# mini32.net
KiCad netlist of a schematic drawn in EAGLE
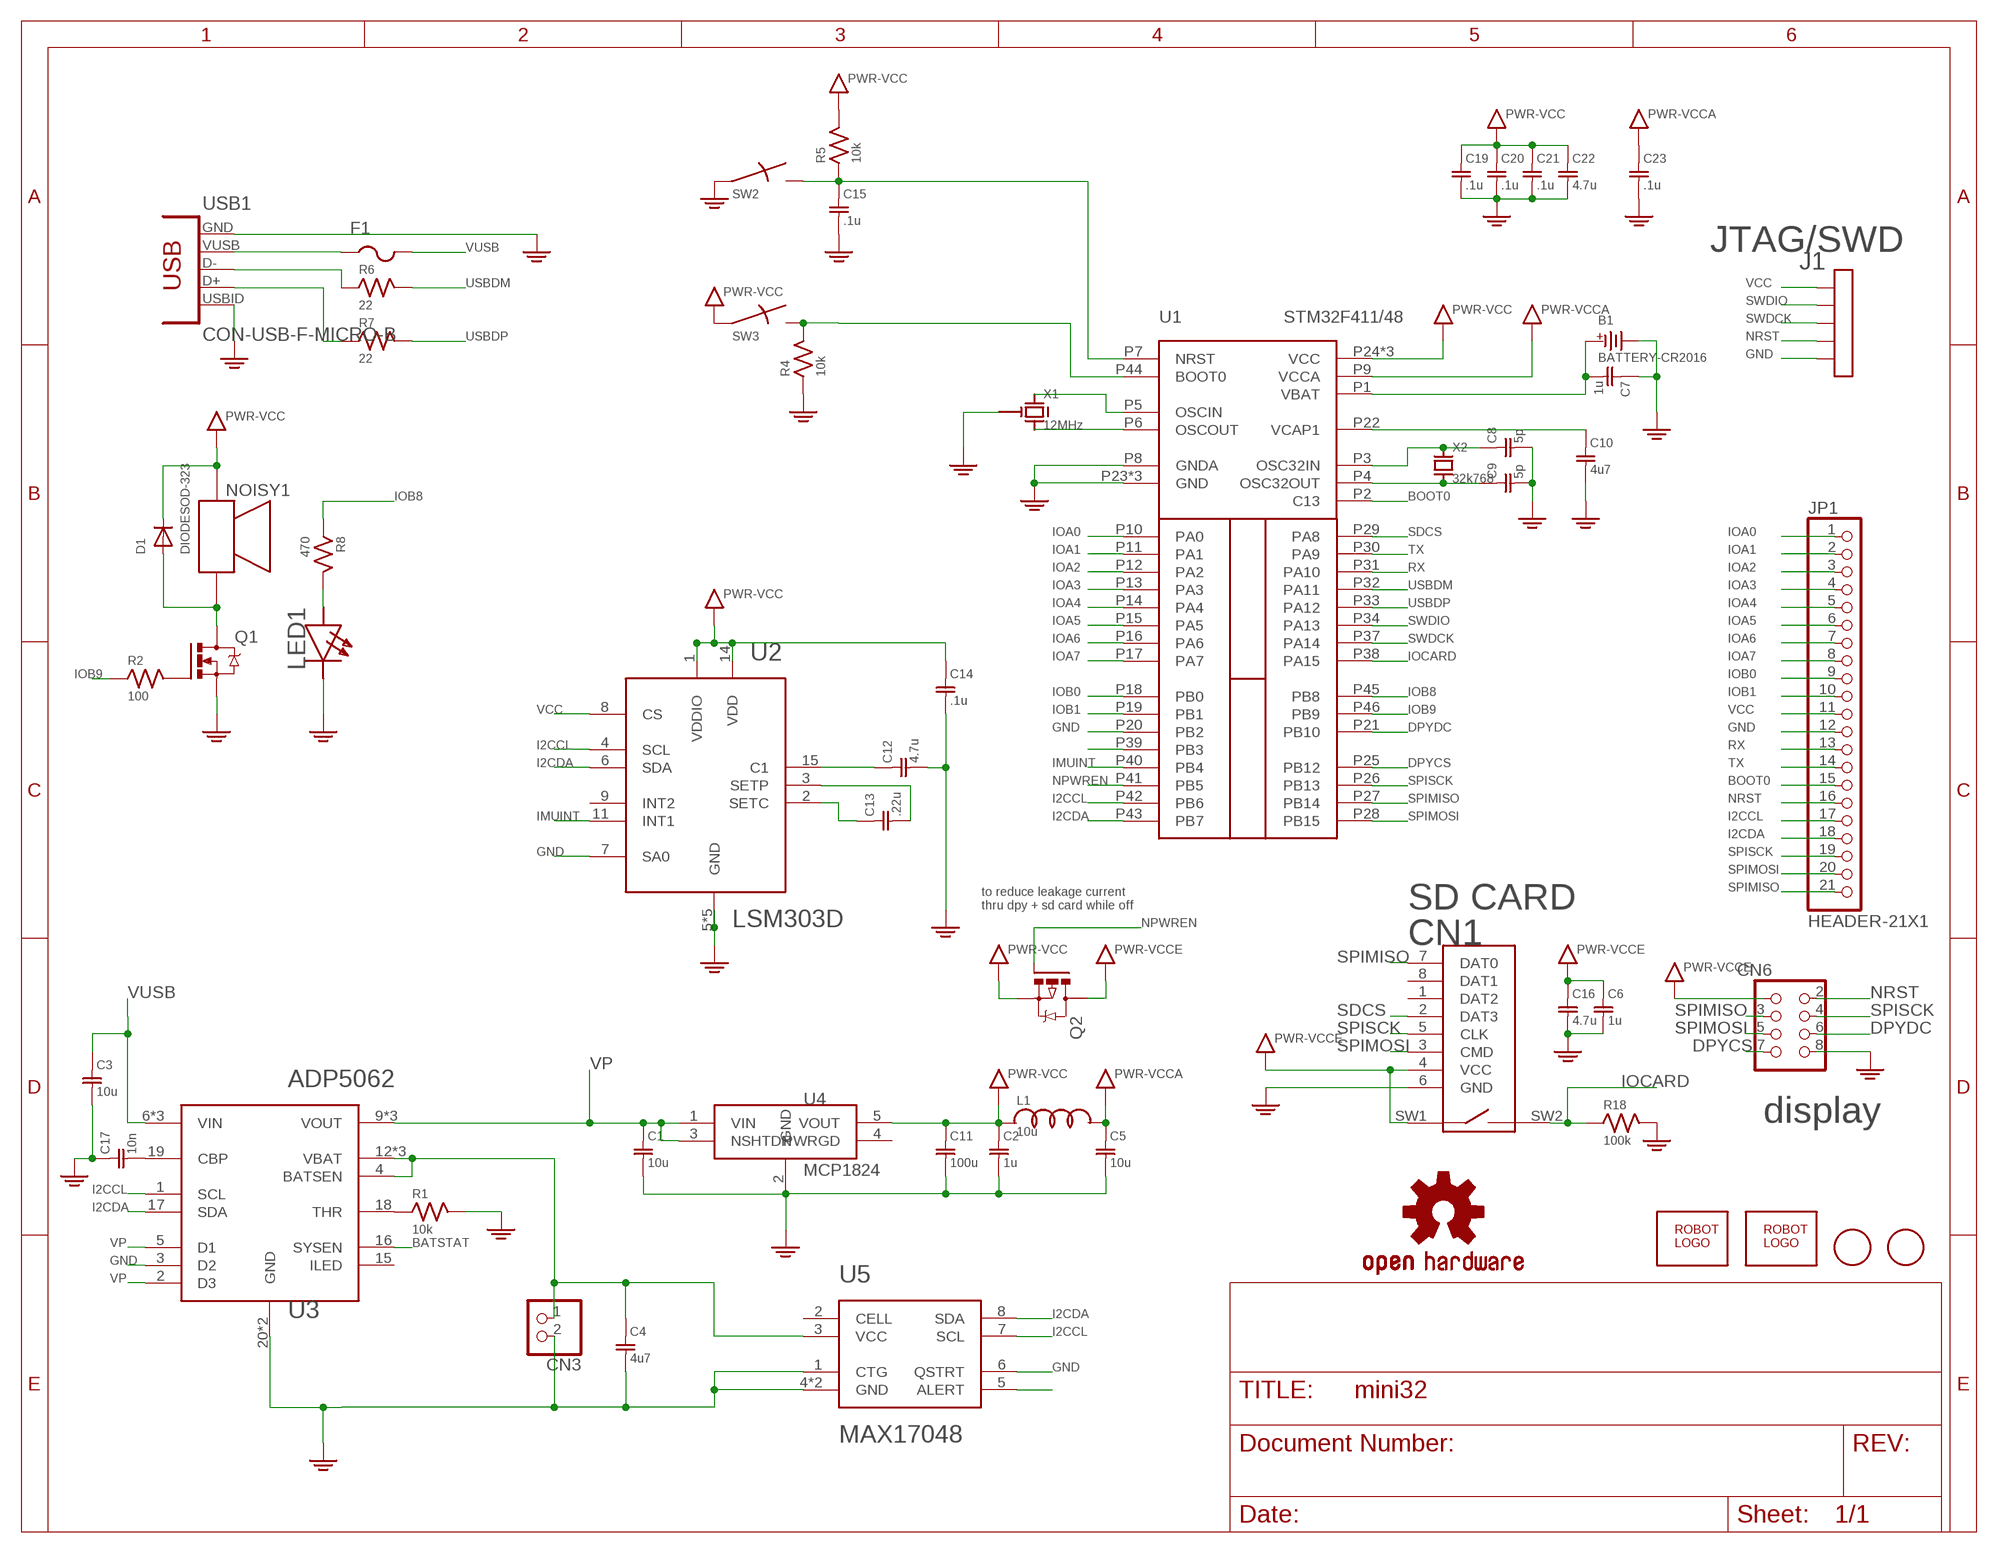
[diagram p0: schematic, sheet 1]

(export (version "E")
  (design (tool "Eeschema 10.0.6"))
  (components
    (comp (ref "B1")
      (value "BATTERY-CR2016")
      (footprint "eagle-import:CR1216")
      (libsource (lib "eagle-import") (part "BATTERY-CR2016"))
    )
    (comp (ref "C1")
      (value "10u")
      (footprint "eagle-import:SMD0603")
      (libsource (lib "eagle-import") (part "C0603"))
    )
    (comp (ref "C2")
      (value "1u")
      (footprint "eagle-import:SMD0603")
      (libsource (lib "eagle-import") (part "C0603"))
    )
    (comp (ref "C3")
      (value "10u")
      (footprint "eagle-import:SMD0603")
      (libsource (lib "eagle-import") (part "C0603"))
    )
    (comp (ref "C4")
      (value "4u7")
      (footprint "eagle-import:SMD0603")
      (libsource (lib "eagle-import") (part "C0603"))
    )
    (comp (ref "C5")
      (value "10u")
      (footprint "eagle-import:SMD0603")
      (libsource (lib "eagle-import") (part "C0603"))
    )
    (comp (ref "C6")
      (value "1u")
      (footprint "eagle-import:SMD0603")
      (libsource (lib "eagle-import") (part "C0603"))
    )
    (comp (ref "C7")
      (value "1u")
      (footprint "eagle-import:SMD0603")
      (libsource (lib "eagle-import") (part "C0603"))
    )
    (comp (ref "C8")
      (value "5p")
      (footprint "eagle-import:SMD0603")
      (libsource (lib "eagle-import") (part "C0603"))
    )
    (comp (ref "C9")
      (value "5p")
      (footprint "eagle-import:SMD0603")
      (libsource (lib "eagle-import") (part "C0603"))
    )
    (comp (ref "C10")
      (value "4u7")
      (footprint "eagle-import:SMD0603")
      (libsource (lib "eagle-import") (part "C0603"))
    )
    (comp (ref "C11")
      (value "100u")
      (footprint "eagle-import:SMD1210")
      (libsource (lib "eagle-import") (part "C1210"))
    )
    (comp (ref "C12")
      (value "4.7u")
      (footprint "eagle-import:SMD0603")
      (libsource (lib "eagle-import") (part "C0603"))
    )
    (comp (ref "C13")
      (value ".22u")
      (footprint "eagle-import:SMD0603")
      (libsource (lib "eagle-import") (part "C0603"))
    )
    (comp (ref "C14")
      (value ".1u")
      (footprint "eagle-import:SMD0603")
      (libsource (lib "eagle-import") (part "C0603"))
    )
    (comp (ref "C15")
      (value ".1u")
      (footprint "eagle-import:SMD0603")
      (libsource (lib "eagle-import") (part "C0603"))
    )
    (comp (ref "C16")
      (value "4.7u")
      (footprint "eagle-import:SMD0603")
      (libsource (lib "eagle-import") (part "C0603"))
    )
    (comp (ref "C17")
      (value "10n")
      (footprint "eagle-import:SMD0603")
      (libsource (lib "eagle-import") (part "C0603"))
    )
    (comp (ref "C19")
      (value ".1u")
      (footprint "eagle-import:SMD0603")
      (libsource (lib "eagle-import") (part "C0603"))
    )
    (comp (ref "C20")
      (value ".1u")
      (footprint "eagle-import:SMD0603")
      (libsource (lib "eagle-import") (part "C0603"))
    )
    (comp (ref "C21")
      (value ".1u")
      (footprint "eagle-import:SMD0603")
      (libsource (lib "eagle-import") (part "C0603"))
    )
    (comp (ref "C22")
      (value "4.7u")
      (footprint "eagle-import:SMD0603")
      (libsource (lib "eagle-import") (part "C0603"))
    )
    (comp (ref "C23")
      (value ".1u")
      (footprint "eagle-import:SMD0603")
      (libsource (lib "eagle-import") (part "C0603"))
    )
    (comp (ref "CN1")
      (value "MICROSDPLAIN")
      (footprint "eagle-import:MICROSD_MOLEX_FRONT_PLAIN")
      (libsource (lib "eagle-import") (part "MICROSDPLAIN"))
    )
    (comp (ref "CN3")
      (value "JST_2PIN-SMT-RA")
      (footprint "eagle-import:JST-PH-2-SMT-RA")
      (libsource (lib "eagle-import") (part "JST_2PIN-SMT-RA"))
    )
    (comp (ref "CN6")
      (value "HEADER-2X4")
      (footprint "eagle-import:HEADER-2X04")
      (libsource (lib "eagle-import") (part "HEADER-2X4"))
    )
    (comp (ref "D1")
      (value "DIODESOD-323")
      (footprint "eagle-import:SOD-323")
      (libsource (lib "eagle-import") (part "DIODESOD-323"))
    )
    (comp (ref "F1")
      (value "PTCFUSE-1206")
      (footprint "eagle-import:R1206")
      (libsource (lib "eagle-import") (part "PTCFUSE-1206"))
    )
    (comp (ref "J1")
      (value "HEADER-5X1")
      (footprint "eagle-import:M127-5X1")
      (libsource (lib "eagle-import") (part "HEADER-5X1"))
    )
    (comp (ref "JP1")
      (value "HEADER-21X1")
      (footprint "eagle-import:HEADER-21X1-PTH")
      (libsource (lib "eagle-import") (part "HEADER-21X1"))
    )
    (comp (ref "L1")
      (value "10u")
      (footprint "eagle-import:SMD0603")
      (libsource (lib "eagle-import") (part "LSMD0603"))
    )
    (comp (ref "LED1")
      (value "white")
      (footprint "eagle-import:SMD0603D")
      (libsource (lib "eagle-import") (part "LED"))
    )
    (comp (ref "LOGO1")
      (value "OSHW-LOGOM")
      (footprint "eagle-import:OSHW-LOGO-M")
      (libsource (lib "eagle-import") (part "OSHW-LOGOM"))
    )
    (comp (ref "NOISY1")
      (value "PUI-5040")
      (footprint "eagle-import:PUI-0540")
      (libsource (lib "eagle-import") (part "PUI-5040"))
    )
    (comp (ref "Q1")
      (value "IRLML6344TRPBF")
      (footprint "eagle-import:SOT-23")
      (libsource (lib "eagle-import") (part "MOSFETSOT-23"))
    )
    (comp (ref "Q2")
      (value "DMP2035U-7")
      (footprint "eagle-import:SOT-23")
      (libsource (lib "eagle-import") (part "MOSFET-P"))
    )
    (comp (ref "R1")
      (value "10k")
      (footprint "eagle-import:SMD0603")
      (libsource (lib "eagle-import") (part "R0603"))
    )
    (comp (ref "R2")
      (value "100")
      (footprint "eagle-import:SMD0603")
      (libsource (lib "eagle-import") (part "R0603"))
    )
    (comp (ref "R4")
      (value "10k")
      (footprint "eagle-import:SMD0603")
      (libsource (lib "eagle-import") (part "R0603"))
    )
    (comp (ref "R5")
      (value "10k")
      (footprint "eagle-import:SMD0603")
      (libsource (lib "eagle-import") (part "R0603"))
    )
    (comp (ref "R6")
      (value "22")
      (footprint "eagle-import:SMD0603")
      (libsource (lib "eagle-import") (part "R0603"))
    )
    (comp (ref "R7")
      (value "22")
      (footprint "eagle-import:SMD0603")
      (libsource (lib "eagle-import") (part "R0603"))
    )
    (comp (ref "R8")
      (value "470")
      (footprint "eagle-import:SMD0603")
      (libsource (lib "eagle-import") (part "R0603"))
    )
    (comp (ref "R18")
      (value "100k")
      (footprint "eagle-import:SMD0603")
      (libsource (lib "eagle-import") (part "R0603"))
    )
    (comp (ref "SW2")
      (value "SWITCHKMR211")
      (footprint "eagle-import:KMR211")
      (libsource (lib "eagle-import") (part "SWITCHKMR211"))
    )
    (comp (ref "SW3")
      (value "SWITCHKMR211")
      (footprint "eagle-import:KMR211")
      (libsource (lib "eagle-import") (part "SWITCHKMR211"))
    )
    (comp (ref "U$1")
      (value "ROBOTMAN-LOGO2")
      (footprint "eagle-import:ROBOTMAN-LOGO2")
      (libsource (lib "eagle-import") (part "ROBOTMAN-LOGO2"))
    )
    (comp (ref "U$2")
      (value "FIDUCIAL")
      (footprint "eagle-import:FIDUCIAL_1MM")
      (libsource (lib "eagle-import") (part "FIDUCIAL"))
    )
    (comp (ref "U$3")
      (value "FIDUCIAL")
      (footprint "eagle-import:FIDUCIAL_1MM")
      (libsource (lib "eagle-import") (part "FIDUCIAL"))
    )
    (comp (ref "U$4")
      (value "ROBOTMAN-LOGO2")
      (footprint "eagle-import:ROBOTMAN-LOGO2")
      (libsource (lib "eagle-import") (part "ROBOTMAN-LOGO2"))
    )
    (comp (ref "U1")
      (value "STM32F411/48")
      (footprint "eagle-import:UQPFN48")
      (libsource (lib "eagle-import") (part "STM32F411/48"))
    )
    (comp (ref "U2")
      (value "LSM303D")
      (footprint "eagle-import:LGA16A")
      (libsource (lib "eagle-import") (part "LSM303D"))
    )
    (comp (ref "U3")
      (value "ADP5062")
      (footprint "eagle-import:LGA20P")
      (libsource (lib "eagle-import") (part "ADP5062"))
    )
    (comp (ref "U4")
      (value "MCP1824")
      (footprint "eagle-import:SOT-23-5")
      (libsource (lib "eagle-import") (part "MCP1824"))
    )
    (comp (ref "U5")
      (value "MAX17048")
      (footprint "eagle-import:TDFN8EP")
      (libsource (lib "eagle-import") (part "MAX17048"))
    )
    (comp (ref "USB1")
      (value "CON-USB-F-MICRO-B")
      (footprint "eagle-import:CONN_USB_MICRO-B")
      (libsource (lib "eagle-import") (part "CON-USB-F-MICRO-B"))
    )
    (comp (ref "X1")
      (value "12MHz")
      (footprint "eagle-import:RESONATOR-CSTCE")
      (libsource (lib "eagle-import") (part "RESONATORCTCE"))
    )
    (comp (ref "X2")
      (value "32k768")
      (footprint "eagle-import:XTAL-32X15")
      (libsource (lib "eagle-import") (part "XTAL32X15"))
    )
  )
  (nets
    (net (code "1") (name "/BATSTAT") (class "Default")
      (node (ref "U3") (pin "16") (pinfunction "SYSEN_16") (pintype "bidirectional"))
    )
    (net (code "2") (name "/BOOT0") (class "Default")
      (node (ref "JP1") (pin "15") (pinfunction "15_15") (pintype "passive"))
      (node (ref "R4") (pin "2") (pinfunction "P$2_2") (pintype "passive"))
      (node (ref "SW3") (pin "2") (pinfunction "P$2_2") (pintype "passive"))
      (node (ref "SW3") (pin "4") (pinfunction "P$2_4") (pintype "passive"))
      (node (ref "U1") (pin "P2") (pinfunction "C13_P2") (pintype "bidirectional"))
      (node (ref "U1") (pin "P44") (pinfunction "BOOT0_P44") (pintype "bidirectional"))
    )
    (net (code "3") (name "/DPYCS") (class "Default")
      (node (ref "CN6") (pin "7") (pinfunction "P$7_7") (pintype "passive"))
      (node (ref "U1") (pin "P25") (pinfunction "PB12_P25") (pintype "bidirectional"))
    )
    (net (code "4") (name "/DPYDC") (class "Default")
      (node (ref "CN6") (pin "6") (pinfunction "P$6_6") (pintype "passive"))
      (node (ref "U1") (pin "P21") (pinfunction "PB10_P21") (pintype "bidirectional"))
    )
    (net (code "5") (name "/I2CCL") (class "Default")
      (node (ref "JP1") (pin "17") (pinfunction "17_17") (pintype "passive"))
      (node (ref "U1") (pin "P42") (pinfunction "PB6_P42") (pintype "bidirectional"))
      (node (ref "U2") (pin "4") (pinfunction "SCL_4") (pintype "bidirectional"))
      (node (ref "U3") (pin "1") (pinfunction "SCL_1") (pintype "bidirectional"))
      (node (ref "U5") (pin "7") (pinfunction "SCL_7") (pintype "bidirectional"))
    )
    (net (code "6") (name "/I2CDA") (class "Default")
      (node (ref "JP1") (pin "18") (pinfunction "18_18") (pintype "passive"))
      (node (ref "U1") (pin "P43") (pinfunction "PB7_P43") (pintype "bidirectional"))
      (node (ref "U2") (pin "6") (pinfunction "SDA_6") (pintype "bidirectional"))
      (node (ref "U3") (pin "17") (pinfunction "SDA_17") (pintype "bidirectional"))
      (node (ref "U5") (pin "8") (pinfunction "SDA_8") (pintype "bidirectional"))
    )
    (net (code "7") (name "/IMUINT") (class "Default")
      (node (ref "U1") (pin "P40") (pinfunction "PB4_P40") (pintype "bidirectional"))
      (node (ref "U2") (pin "11") (pinfunction "INT1_11") (pintype "output"))
    )
    (net (code "8") (name "/IOA0") (class "Default")
      (node (ref "JP1") (pin "1") (pinfunction "1_1") (pintype "passive"))
      (node (ref "U1") (pin "P10") (pinfunction "PA0_P10") (pintype "bidirectional"))
    )
    (net (code "9") (name "/IOA1") (class "Default")
      (node (ref "JP1") (pin "2") (pinfunction "2_2") (pintype "passive"))
      (node (ref "U1") (pin "P11") (pinfunction "PA1_P11") (pintype "bidirectional"))
    )
    (net (code "10") (name "/IOA2") (class "Default")
      (node (ref "JP1") (pin "3") (pinfunction "3_3") (pintype "passive"))
      (node (ref "U1") (pin "P12") (pinfunction "PA2_P12") (pintype "bidirectional"))
    )
    (net (code "11") (name "/IOA3") (class "Default")
      (node (ref "JP1") (pin "4") (pinfunction "4_4") (pintype "passive"))
      (node (ref "U1") (pin "P13") (pinfunction "PA3_P13") (pintype "bidirectional"))
    )
    (net (code "12") (name "/IOA4") (class "Default")
      (node (ref "JP1") (pin "5") (pinfunction "5_5") (pintype "passive"))
      (node (ref "U1") (pin "P14") (pinfunction "PA4_P14") (pintype "bidirectional"))
    )
    (net (code "13") (name "/IOA5") (class "Default")
      (node (ref "JP1") (pin "6") (pinfunction "6_6") (pintype "passive"))
      (node (ref "U1") (pin "P15") (pinfunction "PA5_P15") (pintype "bidirectional"))
    )
    (net (code "14") (name "/IOA6") (class "Default")
      (node (ref "JP1") (pin "7") (pinfunction "7_7") (pintype "passive"))
      (node (ref "U1") (pin "P16") (pinfunction "PA6_P16") (pintype "bidirectional"))
    )
    (net (code "15") (name "/IOA7") (class "Default")
      (node (ref "JP1") (pin "8") (pinfunction "8_8") (pintype "passive"))
      (node (ref "U1") (pin "P17") (pinfunction "PA7_P17") (pintype "bidirectional"))
    )
    (net (code "16") (name "/IOB0") (class "Default")
      (node (ref "JP1") (pin "9") (pinfunction "9_9") (pintype "passive"))
      (node (ref "U1") (pin "P18") (pinfunction "PB0_P18") (pintype "bidirectional"))
    )
    (net (code "17") (name "/IOB1") (class "Default")
      (node (ref "JP1") (pin "10") (pinfunction "10_10") (pintype "passive"))
      (node (ref "U1") (pin "P19") (pinfunction "PB1_P19") (pintype "bidirectional"))
    )
    (net (code "18") (name "/IOB8") (class "Default")
      (node (ref "R8") (pin "1") (pinfunction "P$1_1") (pintype "passive"))
      (node (ref "U1") (pin "P45") (pinfunction "PB8_P45") (pintype "bidirectional"))
    )
    (net (code "19") (name "/IOB9") (class "Default")
      (node (ref "R2") (pin "1") (pinfunction "P$1_1") (pintype "passive"))
      (node (ref "U1") (pin "P46") (pinfunction "PB9_P46") (pintype "bidirectional"))
    )
    (net (code "20") (name "/IOCARD") (class "Default")
      (node (ref "CN1") (pin "SW2") (pinfunction "SW2_SW2") (pintype "bidirectional"))
      (node (ref "R18") (pin "1") (pinfunction "P$1_1") (pintype "passive"))
      (node (ref "U1") (pin "P38") (pinfunction "PA15_P38") (pintype "bidirectional"))
    )
    (net (code "21") (name "/NPWREN") (class "Default")
      (node (ref "Q2") (pin "1") (pinfunction "G_1") (pintype "passive"))
      (node (ref "U1") (pin "P41") (pinfunction "PB5_P41") (pintype "bidirectional"))
    )
    (net (code "22") (name "/NRST") (class "Default")
      (node (ref "C15") (pin "1") (pinfunction "P$1_1") (pintype "passive"))
      (node (ref "CN6") (pin "2") (pinfunction "P$2_2") (pintype "passive"))
      (node (ref "J1") (pin "P$4") (pinfunction "4_P$4") (pintype "bidirectional"))
      (node (ref "JP1") (pin "16") (pinfunction "16_16") (pintype "passive"))
      (node (ref "R5") (pin "1") (pinfunction "P$1_1") (pintype "passive"))
      (node (ref "SW2") (pin "2") (pinfunction "P$2_2") (pintype "passive"))
      (node (ref "SW2") (pin "4") (pinfunction "P$2_4") (pintype "passive"))
      (node (ref "U1") (pin "P7") (pinfunction "NRST_P7") (pintype "bidirectional"))
    )
    (net (code "23") (name "/RX") (class "Default")
      (node (ref "JP1") (pin "13") (pinfunction "13_13") (pintype "passive"))
      (node (ref "U1") (pin "P31") (pinfunction "PA10_P31") (pintype "bidirectional"))
    )
    (net (code "24") (name "/SDCS") (class "Default")
      (node (ref "CN1") (pin "2") (pinfunction "DAT3_2") (pintype "bidirectional"))
      (node (ref "U1") (pin "P29") (pinfunction "PA8_P29") (pintype "bidirectional"))
    )
    (net (code "25") (name "/SPIMISO") (class "Default")
      (node (ref "CN1") (pin "7") (pinfunction "DAT0_7") (pintype "bidirectional"))
      (node (ref "CN6") (pin "3") (pinfunction "P$3_3") (pintype "passive"))
      (node (ref "JP1") (pin "21") (pinfunction "21_21") (pintype "passive"))
      (node (ref "U1") (pin "P27") (pinfunction "PB14_P27") (pintype "bidirectional"))
    )
    (net (code "26") (name "/SPIMOSI") (class "Default")
      (node (ref "CN1") (pin "3") (pinfunction "CMD_3") (pintype "bidirectional"))
      (node (ref "CN6") (pin "5") (pinfunction "P$5_5") (pintype "passive"))
      (node (ref "JP1") (pin "20") (pinfunction "20_20") (pintype "passive"))
      (node (ref "U1") (pin "P28") (pinfunction "PB15_P28") (pintype "bidirectional"))
    )
    (net (code "27") (name "/SPISCK") (class "Default")
      (node (ref "CN1") (pin "5") (pinfunction "CLK_5") (pintype "bidirectional"))
      (node (ref "CN6") (pin "4") (pinfunction "P$4_4") (pintype "passive"))
      (node (ref "JP1") (pin "19") (pinfunction "19_19") (pintype "passive"))
      (node (ref "U1") (pin "P26") (pinfunction "PB13_P26") (pintype "bidirectional"))
    )
    (net (code "28") (name "/SWDCK") (class "Default")
      (node (ref "J1") (pin "P$3") (pinfunction "3_P$3") (pintype "bidirectional"))
      (node (ref "U1") (pin "P37") (pinfunction "PA14_P37") (pintype "bidirectional"))
    )
    (net (code "29") (name "/SWDIO") (class "Default")
      (node (ref "J1") (pin "P$2") (pinfunction "2_P$2") (pintype "bidirectional"))
      (node (ref "U1") (pin "P34") (pinfunction "PA13_P34") (pintype "bidirectional"))
    )
    (net (code "30") (name "/TX") (class "Default")
      (node (ref "JP1") (pin "14") (pinfunction "14_14") (pintype "passive"))
      (node (ref "U1") (pin "P30") (pinfunction "PA9_P30") (pintype "bidirectional"))
    )
    (net (code "31") (name "/USBDM") (class "Default")
      (node (ref "R6") (pin "2") (pinfunction "P$2_2") (pintype "passive"))
      (node (ref "U1") (pin "P32") (pinfunction "PA11_P32") (pintype "bidirectional"))
    )
    (net (code "32") (name "/USBDP") (class "Default")
      (node (ref "R7") (pin "2") (pinfunction "P$2_2") (pintype "passive"))
      (node (ref "U1") (pin "P33") (pinfunction "PA12_P33") (pintype "bidirectional"))
    )
    (net (code "33") (name "/VP") (class "Default")
      (node (ref "C1") (pin "1") (pinfunction "P$1_1") (pintype "passive"))
      (node (ref "U3") (pin "10") (pinfunction "VOUT_10") (pintype "bidirectional"))
      (node (ref "U3") (pin "11") (pinfunction "VOUT_11") (pintype "bidirectional"))
      (node (ref "U3") (pin "2") (pinfunction "D3_2") (pintype "bidirectional"))
      (node (ref "U3") (pin "5") (pinfunction "D1_5") (pintype "bidirectional"))
      (node (ref "U3") (pin "9") (pinfunction "VOUT_9") (pintype "bidirectional"))
      (node (ref "U4") (pin "1") (pinfunction "VIN_1") (pintype "bidirectional"))
      (node (ref "U4") (pin "3") (pinfunction "NSHTDN_3") (pintype "bidirectional"))
    )
    (net (code "34") (name "/VUSB") (class "Default")
      (node (ref "C3") (pin "1") (pinfunction "P$1_1") (pintype "passive"))
      (node (ref "F1") (pin "2") (pinfunction "2_2") (pintype "passive"))
      (node (ref "U3") (pin "6") (pinfunction "VIN_6") (pintype "bidirectional"))
      (node (ref "U3") (pin "7") (pinfunction "VIN_7") (pintype "bidirectional"))
      (node (ref "U3") (pin "8") (pinfunction "VIN_8") (pintype "bidirectional"))
    )
    (net (code "35") (name "Net-(C4-P$1)") (class "Default")
      (node (ref "C4") (pin "1") (pinfunction "P$1_1") (pintype "passive"))
      (node (ref "CN3") (pin "1") (pinfunction "2_1") (pintype "passive"))
      (node (ref "U3") (pin "12") (pinfunction "VBAT_12") (pintype "bidirectional"))
      (node (ref "U3") (pin "13") (pinfunction "VBAT_13") (pintype "bidirectional"))
      (node (ref "U3") (pin "14") (pinfunction "VBAT_14") (pintype "bidirectional"))
      (node (ref "U3") (pin "4") (pinfunction "BATSEN_4") (pintype "bidirectional"))
      (node (ref "U5") (pin "3") (pinfunction "VCC_3") (pintype "bidirectional"))
    )
    (net (code "36") (name "Net-(C7-P$2)") (class "Default")
      (node (ref "B1") (pin "PLUS1") (pinfunction "P_PLUS1") (pintype "bidirectional"))
      (node (ref "B1") (pin "PLUS2") (pinfunction "P_PLUS2") (pintype "bidirectional"))
      (node (ref "C7") (pin "2") (pinfunction "P$2_2") (pintype "passive"))
      (node (ref "U1") (pin "P1") (pinfunction "VBAT_P1") (pintype "bidirectional"))
    )
    (net (code "37") (name "Net-(C8-P$1)") (class "Default")
      (node (ref "C8") (pin "1") (pinfunction "P$1_1") (pintype "passive"))
      (node (ref "U1") (pin "P3") (pinfunction "OSC32IN_P3") (pintype "bidirectional"))
      (node (ref "X2") (pin "P$1") (pinfunction "P$1_P$1") (pintype "passive"))
    )
    (net (code "38") (name "Net-(C9-P$1)") (class "Default")
      (node (ref "C9") (pin "1") (pinfunction "P$1_1") (pintype "passive"))
      (node (ref "U1") (pin "P4") (pinfunction "OSC32OUT_P4") (pintype "bidirectional"))
      (node (ref "X2") (pin "P$2") (pinfunction "P$2_P$2") (pintype "passive"))
    )
    (net (code "39") (name "Net-(C10-P$1)") (class "Default")
      (node (ref "C10") (pin "1") (pinfunction "P$1_1") (pintype "passive"))
      (node (ref "U1") (pin "P22") (pinfunction "VCAP1_P22") (pintype "bidirectional"))
    )
    (net (code "40") (name "Net-(C12-P$1)") (class "Default")
      (node (ref "C12") (pin "1") (pinfunction "P$1_1") (pintype "passive"))
      (node (ref "U2") (pin "15") (pinfunction "C1_15") (pintype "bidirectional"))
    )
    (net (code "41") (name "Net-(C13-P$1)") (class "Default")
      (node (ref "C13") (pin "1") (pinfunction "P$1_1") (pintype "passive"))
      (node (ref "U2") (pin "2") (pinfunction "SETC_2") (pintype "bidirectional"))
    )
    (net (code "42") (name "Net-(C13-P$2)") (class "Default")
      (node (ref "C13") (pin "2") (pinfunction "P$2_2") (pintype "passive"))
      (node (ref "U2") (pin "3") (pinfunction "SETP_3") (pintype "bidirectional"))
    )
    (net (code "43") (name "Net-(C17-P$2)") (class "Default")
      (node (ref "C17") (pin "2") (pinfunction "P$2_2") (pintype "passive"))
      (node (ref "U3") (pin "19") (pinfunction "CBP_19") (pintype "bidirectional"))
    )
    (net (code "44") (name "Net-(Q1-D)") (class "Default")
      (node (ref "D1") (pin "A") (pinfunction "A_A") (pintype "passive"))
      (node (ref "NOISY1") (pin "P2") (pinfunction "P2_P2") (pintype "input"))
      (node (ref "Q1") (pin "3") (pinfunction "D_3") (pintype "passive"))
    )
    (net (code "45") (name "Net-(Q1-G)") (class "Default")
      (node (ref "Q1") (pin "1") (pinfunction "G_1") (pintype "passive"))
      (node (ref "R2") (pin "2") (pinfunction "P$2_2") (pintype "passive"))
    )
    (net (code "46") (name "Net-(R1-P$1)") (class "Default")
      (node (ref "R1") (pin "1") (pinfunction "P$1_1") (pintype "passive"))
      (node (ref "U3") (pin "18") (pinfunction "THR_18") (pintype "bidirectional"))
    )
    (net (code "47") (name "Net-(R6-P$1)") (class "Default")
      (node (ref "R6") (pin "1") (pinfunction "P$1_1") (pintype "passive"))
      (node (ref "USB1") (pin "P2") (pinfunction "D-_P2") (pintype "bidirectional"))
    )
    (net (code "48") (name "Net-(R7-P$1)") (class "Default")
      (node (ref "R7") (pin "1") (pinfunction "P$1_1") (pintype "passive"))
      (node (ref "USB1") (pin "P3") (pinfunction "D+_P3") (pintype "bidirectional"))
    )
    (net (code "49") (name "Net-(R8-P$2)") (class "Default")
      (node (ref "LED1") (pin "A") (pinfunction "A_A") (pintype "passive"))
      (node (ref "R8") (pin "2") (pinfunction "P$2_2") (pintype "passive"))
    )
    (net (code "50") (name "Net-(U1-OSCIN)") (class "Default")
      (node (ref "U1") (pin "P5") (pinfunction "OSCIN_P5") (pintype "bidirectional"))
      (node (ref "X1") (pin "1") (pinfunction "X1_1") (pintype "passive"))
    )
    (net (code "51") (name "Net-(U1-OSCOUT)") (class "Default")
      (node (ref "U1") (pin "P6") (pinfunction "OSCOUT_P6") (pintype "bidirectional"))
      (node (ref "X1") (pin "3") (pinfunction "X2_3") (pintype "passive"))
    )
    (net (code "52") (name "Net-(USB1B-VUSB)") (class "Default")
      (node (ref "F1") (pin "1") (pinfunction "1_1") (pintype "passive"))
      (node (ref "USB1") (pin "P1") (pinfunction "VUSB_P1") (pintype "bidirectional"))
    )
    (net (code "53") (name "PWR-GND") (class "Default")
      (node (ref "B1") (pin "MINUS") (pinfunction "M_MINUS") (pintype "bidirectional"))
      (node (ref "C1") (pin "2") (pinfunction "P$2_2") (pintype "passive"))
      (node (ref "C10") (pin "2") (pinfunction "P$2_2") (pintype "passive"))
      (node (ref "C11") (pin "2") (pinfunction "P$2_2") (pintype "passive"))
      (node (ref "C12") (pin "2") (pinfunction "P$2_2") (pintype "passive"))
      (node (ref "C14") (pin "2") (pinfunction "P$2_2") (pintype "passive"))
      (node (ref "C15") (pin "2") (pinfunction "P$2_2") (pintype "passive"))
      (node (ref "C16") (pin "2") (pinfunction "P$2_2") (pintype "passive"))
      (node (ref "C17") (pin "1") (pinfunction "P$1_1") (pintype "passive"))
      (node (ref "C19") (pin "2") (pinfunction "P$2_2") (pintype "passive"))
      (node (ref "C2") (pin "2") (pinfunction "P$2_2") (pintype "passive"))
      (node (ref "C20") (pin "2") (pinfunction "P$2_2") (pintype "passive"))
      (node (ref "C21") (pin "2") (pinfunction "P$2_2") (pintype "passive"))
      (node (ref "C22") (pin "2") (pinfunction "P$2_2") (pintype "passive"))
      (node (ref "C23") (pin "2") (pinfunction "P$2_2") (pintype "passive"))
      (node (ref "C3") (pin "2") (pinfunction "P$2_2") (pintype "passive"))
      (node (ref "C4") (pin "2") (pinfunction "P$2_2") (pintype "passive"))
      (node (ref "C5") (pin "2") (pinfunction "P$2_2") (pintype "passive"))
      (node (ref "C6") (pin "2") (pinfunction "P$2_2") (pintype "passive"))
      (node (ref "C7") (pin "1") (pinfunction "P$1_1") (pintype "passive"))
      (node (ref "C8") (pin "2") (pinfunction "P$2_2") (pintype "passive"))
      (node (ref "C9") (pin "2") (pinfunction "P$2_2") (pintype "passive"))
      (node (ref "CN1") (pin "6") (pinfunction "GND_6") (pintype "bidirectional"))
      (node (ref "CN3") (pin "2") (pinfunction "1_2") (pintype "passive"))
      (node (ref "CN6") (pin "8") (pinfunction "P$8_8") (pintype "passive"))
      (node (ref "J1") (pin "P$5") (pinfunction "5_P$5") (pintype "bidirectional"))
      (node (ref "JP1") (pin "12") (pinfunction "12_12") (pintype "passive"))
      (node (ref "LED1") (pin "C") (pinfunction "C_C") (pintype "passive"))
      (node (ref "Q1") (pin "2") (pinfunction "S_2") (pintype "passive"))
      (node (ref "R1") (pin "2") (pinfunction "P$2_2") (pintype "passive"))
      (node (ref "R18") (pin "2") (pinfunction "P$2_2") (pintype "passive"))
      (node (ref "R4") (pin "1") (pinfunction "P$1_1") (pintype "passive"))
      (node (ref "SW2") (pin "1") (pinfunction "P$1_1") (pintype "passive"))
      (node (ref "SW2") (pin "3") (pinfunction "P$1_3") (pintype "passive"))
      (node (ref "U1") (pin "P20") (pinfunction "PB2_P20") (pintype "bidirectional"))
      (node (ref "U1") (pin "P23") (pinfunction "GND_P23") (pintype "bidirectional"))
      (node (ref "U1") (pin "P35") (pinfunction "GND_P35") (pintype "bidirectional"))
      (node (ref "U1") (pin "P47") (pinfunction "GND_P47") (pintype "bidirectional"))
      (node (ref "U1") (pin "P8") (pinfunction "GNDA_P8") (pintype "bidirectional"))
      (node (ref "U2") (pin "10") (pinfunction "GND_10") (pintype "bidirectional"))
      (node (ref "U2") (pin "12") (pinfunction "GND_12") (pintype "bidirectional"))
      (node (ref "U2") (pin "13") (pinfunction "GND_13") (pintype "bidirectional"))
      (node (ref "U2") (pin "16") (pinfunction "GND_16") (pintype "bidirectional"))
      (node (ref "U2") (pin "5") (pinfunction "GND_5") (pintype "bidirectional"))
      (node (ref "U2") (pin "7") (pinfunction "SA0_7") (pintype "bidirectional"))
      (node (ref "U3") (pin "20") (pinfunction "GND_20") (pintype "bidirectional"))
      (node (ref "U3") (pin "3") (pinfunction "D2_3") (pintype "bidirectional"))
      (node (ref "U3") (pin "PAD") (pinfunction "GND_PAD") (pintype "bidirectional"))
      (node (ref "U4") (pin "2") (pinfunction "GND_2") (pintype "bidirectional"))
      (node (ref "U5") (pin "1") (pinfunction "CTG_1") (pintype "bidirectional"))
      (node (ref "U5") (pin "4") (pinfunction "GND_4") (pintype "bidirectional"))
      (node (ref "U5") (pin "6") (pinfunction "QSTRT_6") (pintype "bidirectional"))
      (node (ref "U5") (pin "PAD") (pinfunction "GND_PAD") (pintype "bidirectional"))
      (node (ref "USB1") (pin "P4") (pinfunction "USBID_P4") (pintype "bidirectional"))
      (node (ref "USB1") (pin "P5") (pinfunction "GND_P5") (pintype "bidirectional"))
      (node (ref "X1") (pin "2") (pinfunction "G_2") (pintype "input"))
    )
    (net (code "54") (name "PWR-VCC") (class "Default")
      (node (ref "C11") (pin "1") (pinfunction "P$1_1") (pintype "passive"))
      (node (ref "C14") (pin "1") (pinfunction "P$1_1") (pintype "passive"))
      (node (ref "C19") (pin "1") (pinfunction "P$1_1") (pintype "passive"))
      (node (ref "C2") (pin "1") (pinfunction "P$1_1") (pintype "passive"))
      (node (ref "C20") (pin "1") (pinfunction "P$1_1") (pintype "passive"))
      (node (ref "C21") (pin "1") (pinfunction "P$1_1") (pintype "passive"))
      (node (ref "C22") (pin "1") (pinfunction "P$1_1") (pintype "passive"))
      (node (ref "D1") (pin "C") (pinfunction "C_C") (pintype "passive"))
      (node (ref "J1") (pin "P$1") (pinfunction "1_P$1") (pintype "bidirectional"))
      (node (ref "JP1") (pin "11") (pinfunction "11_11") (pintype "passive"))
      (node (ref "L1") (pin "1") (pinfunction "P$1_1") (pintype "passive"))
      (node (ref "NOISY1") (pin "P1") (pinfunction "P1_P1") (pintype "input"))
      (node (ref "Q2") (pin "2") (pinfunction "S_2") (pintype "passive"))
      (node (ref "R5") (pin "2") (pinfunction "P$2_2") (pintype "passive"))
      (node (ref "SW3") (pin "1") (pinfunction "P$1_1") (pintype "passive"))
      (node (ref "SW3") (pin "3") (pinfunction "P$1_3") (pintype "passive"))
      (node (ref "U1") (pin "P24") (pinfunction "VCC_P24") (pintype "bidirectional"))
      (node (ref "U1") (pin "P36") (pinfunction "VCC_P36") (pintype "bidirectional"))
      (node (ref "U1") (pin "P48") (pinfunction "VCC_P48") (pintype "bidirectional"))
      (node (ref "U2") (pin "1") (pinfunction "VDDIO_1") (pintype "bidirectional"))
      (node (ref "U2") (pin "14") (pinfunction "VDD_14") (pintype "bidirectional"))
      (node (ref "U2") (pin "8") (pinfunction "CS_8") (pintype "bidirectional"))
      (node (ref "U4") (pin "5") (pinfunction "VOUT_5") (pintype "bidirectional"))
    )
    (net (code "55") (name "PWR-VCCA") (class "Default")
      (node (ref "C23") (pin "1") (pinfunction "P$1_1") (pintype "passive"))
      (node (ref "C5") (pin "1") (pinfunction "P$1_1") (pintype "passive"))
      (node (ref "L1") (pin "2") (pinfunction "P$2_2") (pintype "passive"))
      (node (ref "U1") (pin "P9") (pinfunction "VCCA_P9") (pintype "bidirectional"))
    )
    (net (code "56") (name "PWR-VCCE") (class "Default")
      (node (ref "C16") (pin "1") (pinfunction "P$1_1") (pintype "passive"))
      (node (ref "C6") (pin "1") (pinfunction "P$1_1") (pintype "passive"))
      (node (ref "CN1") (pin "4") (pinfunction "VCC_4") (pintype "bidirectional"))
      (node (ref "CN1") (pin "SW1") (pinfunction "SW1_SW1") (pintype "bidirectional"))
      (node (ref "CN6") (pin "1") (pinfunction "P$1_1") (pintype "passive"))
      (node (ref "Q2") (pin "3") (pinfunction "D_3") (pintype "passive"))
    )
    (net (code "57") (name "unconnected-(CN1-DAT1-Pad8)") (class "Default")
      (node (ref "CN1") (pin "8") (pinfunction "DAT1_8") (pintype "bidirectional"))
    )
    (net (code "58") (name "unconnected-(CN1-DAT2-Pad1)") (class "Default")
      (node (ref "CN1") (pin "1") (pinfunction "DAT2_1") (pintype "bidirectional"))
    )
    (net (code "59") (name "unconnected-(U1-PB3-PadP39)") (class "Default")
      (node (ref "U1") (pin "P39") (pinfunction "PB3_P39") (pintype "bidirectional"))
    )
    (net (code "60") (name "unconnected-(U2-INT2-Pad9)") (class "Default")
      (node (ref "U2") (pin "9") (pinfunction "INT2_9") (pintype "output"))
    )
    (net (code "61") (name "unconnected-(U3-ILED-Pad15)") (class "Default")
      (node (ref "U3") (pin "15") (pinfunction "ILED_15") (pintype "bidirectional"))
    )
    (net (code "62") (name "unconnected-(U4-PWRGD-Pad4)") (class "Default")
      (node (ref "U4") (pin "4") (pinfunction "PWRGD_4") (pintype "bidirectional"))
    )
    (net (code "63") (name "unconnected-(U5-ALERT-Pad5)") (class "Default")
      (node (ref "U5") (pin "5") (pinfunction "ALERT_5") (pintype "bidirectional"))
    )
    (net (code "64") (name "unconnected-(U5-CELL-Pad2)") (class "Default")
      (node (ref "U5") (pin "2") (pinfunction "CELL_2") (pintype "bidirectional"))
    )
  )
)
